# SAFETY_SWITCH.net
KiCad netlist of a schematic drawn in Altium Designer
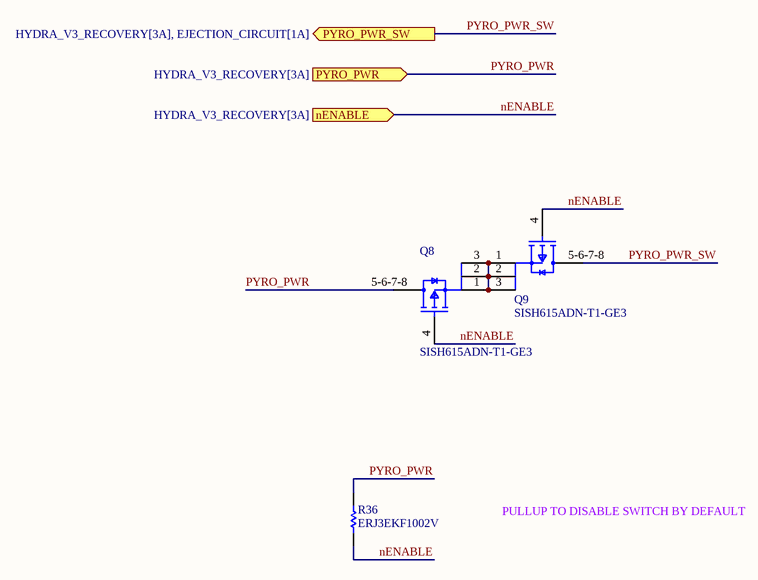
[diagram p0: SAFETY_SWITCH.SchDoc]

(export (version "E")
  (design (tool "Eeschema 10.0.6"))
  (components
    (comp (ref "Q8")
      (value "SISH615ADN-T1-GE3")
      (footprint "SISH615ADN-T1-GE3-Footprint-1")
      (description "Trans MOSFET P-CH 20V 22.1A 8-Pin PowerPAK 1212 EP T/R")
      (libsource (lib "Space Concordia") (part "CMP-013-00036-4"))
    )
    (comp (ref "Q9")
      (value "SISH615ADN-T1-GE3")
      (footprint "SISH615ADN-T1-GE3-Footprint-1")
      (description "Trans MOSFET P-CH 20V 22.1A 8-Pin PowerPAK 1212 EP T/R")
      (libsource (lib "Space Concordia") (part "CMP-013-00036-4"))
    )
    (comp (ref "R36")
      (value "ERJ3EKF1002V")
      (footprint "RESC1609X55X30LL15T15")
      (description "Chip Resistor, 10 KOhm, +/- 1%, 0.1 W, -55 to 155 degC, 0603 (1608 Metric), RoHS, Tape and Reel")
      (fields (field (name "TOLERANCE") "1%") (field (name "MANUFACTURER") "Panasonic"))
      (libsource (lib "Altium Content Vault") (part "RES-2"))
    )
  )
  (nets
    (net (code "1") (name "/PYRO_PWR") (class "Default")
      (node (ref "Q8") (pin "5-6-7-8") (pinfunction "D_5-6-7-8") (pintype "passive"))
      (node (ref "R36") (pin "1") (pinfunction "1_1") (pintype "passive"))
    )
    (net (code "2") (name "/PYRO_PWR_SW") (class "Default")
      (node (ref "Q9") (pin "5-6-7-8") (pinfunction "D_5-6-7-8") (pintype "passive"))
    )
    (net (code "3") (name "/nENABLE") (class "Default")
      (node (ref "Q8") (pin "4") (pinfunction "G_4") (pintype "passive"))
      (node (ref "Q9") (pin "4") (pinfunction "G_4") (pintype "passive"))
      (node (ref "R36") (pin "2") (pinfunction "2_2") (pintype "passive"))
    )
    (net (code "4") (name "Net-(Q8-S-Pad1)") (class "Default")
      (node (ref "Q8") (pin "1") (pinfunction "S_1") (pintype "passive"))
      (node (ref "Q8") (pin "2") (pinfunction "S_2") (pintype "passive"))
      (node (ref "Q8") (pin "3") (pinfunction "S_3") (pintype "passive"))
      (node (ref "Q9") (pin "1") (pinfunction "S_1") (pintype "passive"))
      (node (ref "Q9") (pin "2") (pinfunction "S_2") (pintype "passive"))
      (node (ref "Q9") (pin "3") (pinfunction "S_3") (pintype "passive"))
    )
  )
)
